# MP_MB_2014-12-17_B.net
KiCad netlist of a schematic drawn in Altium Designer
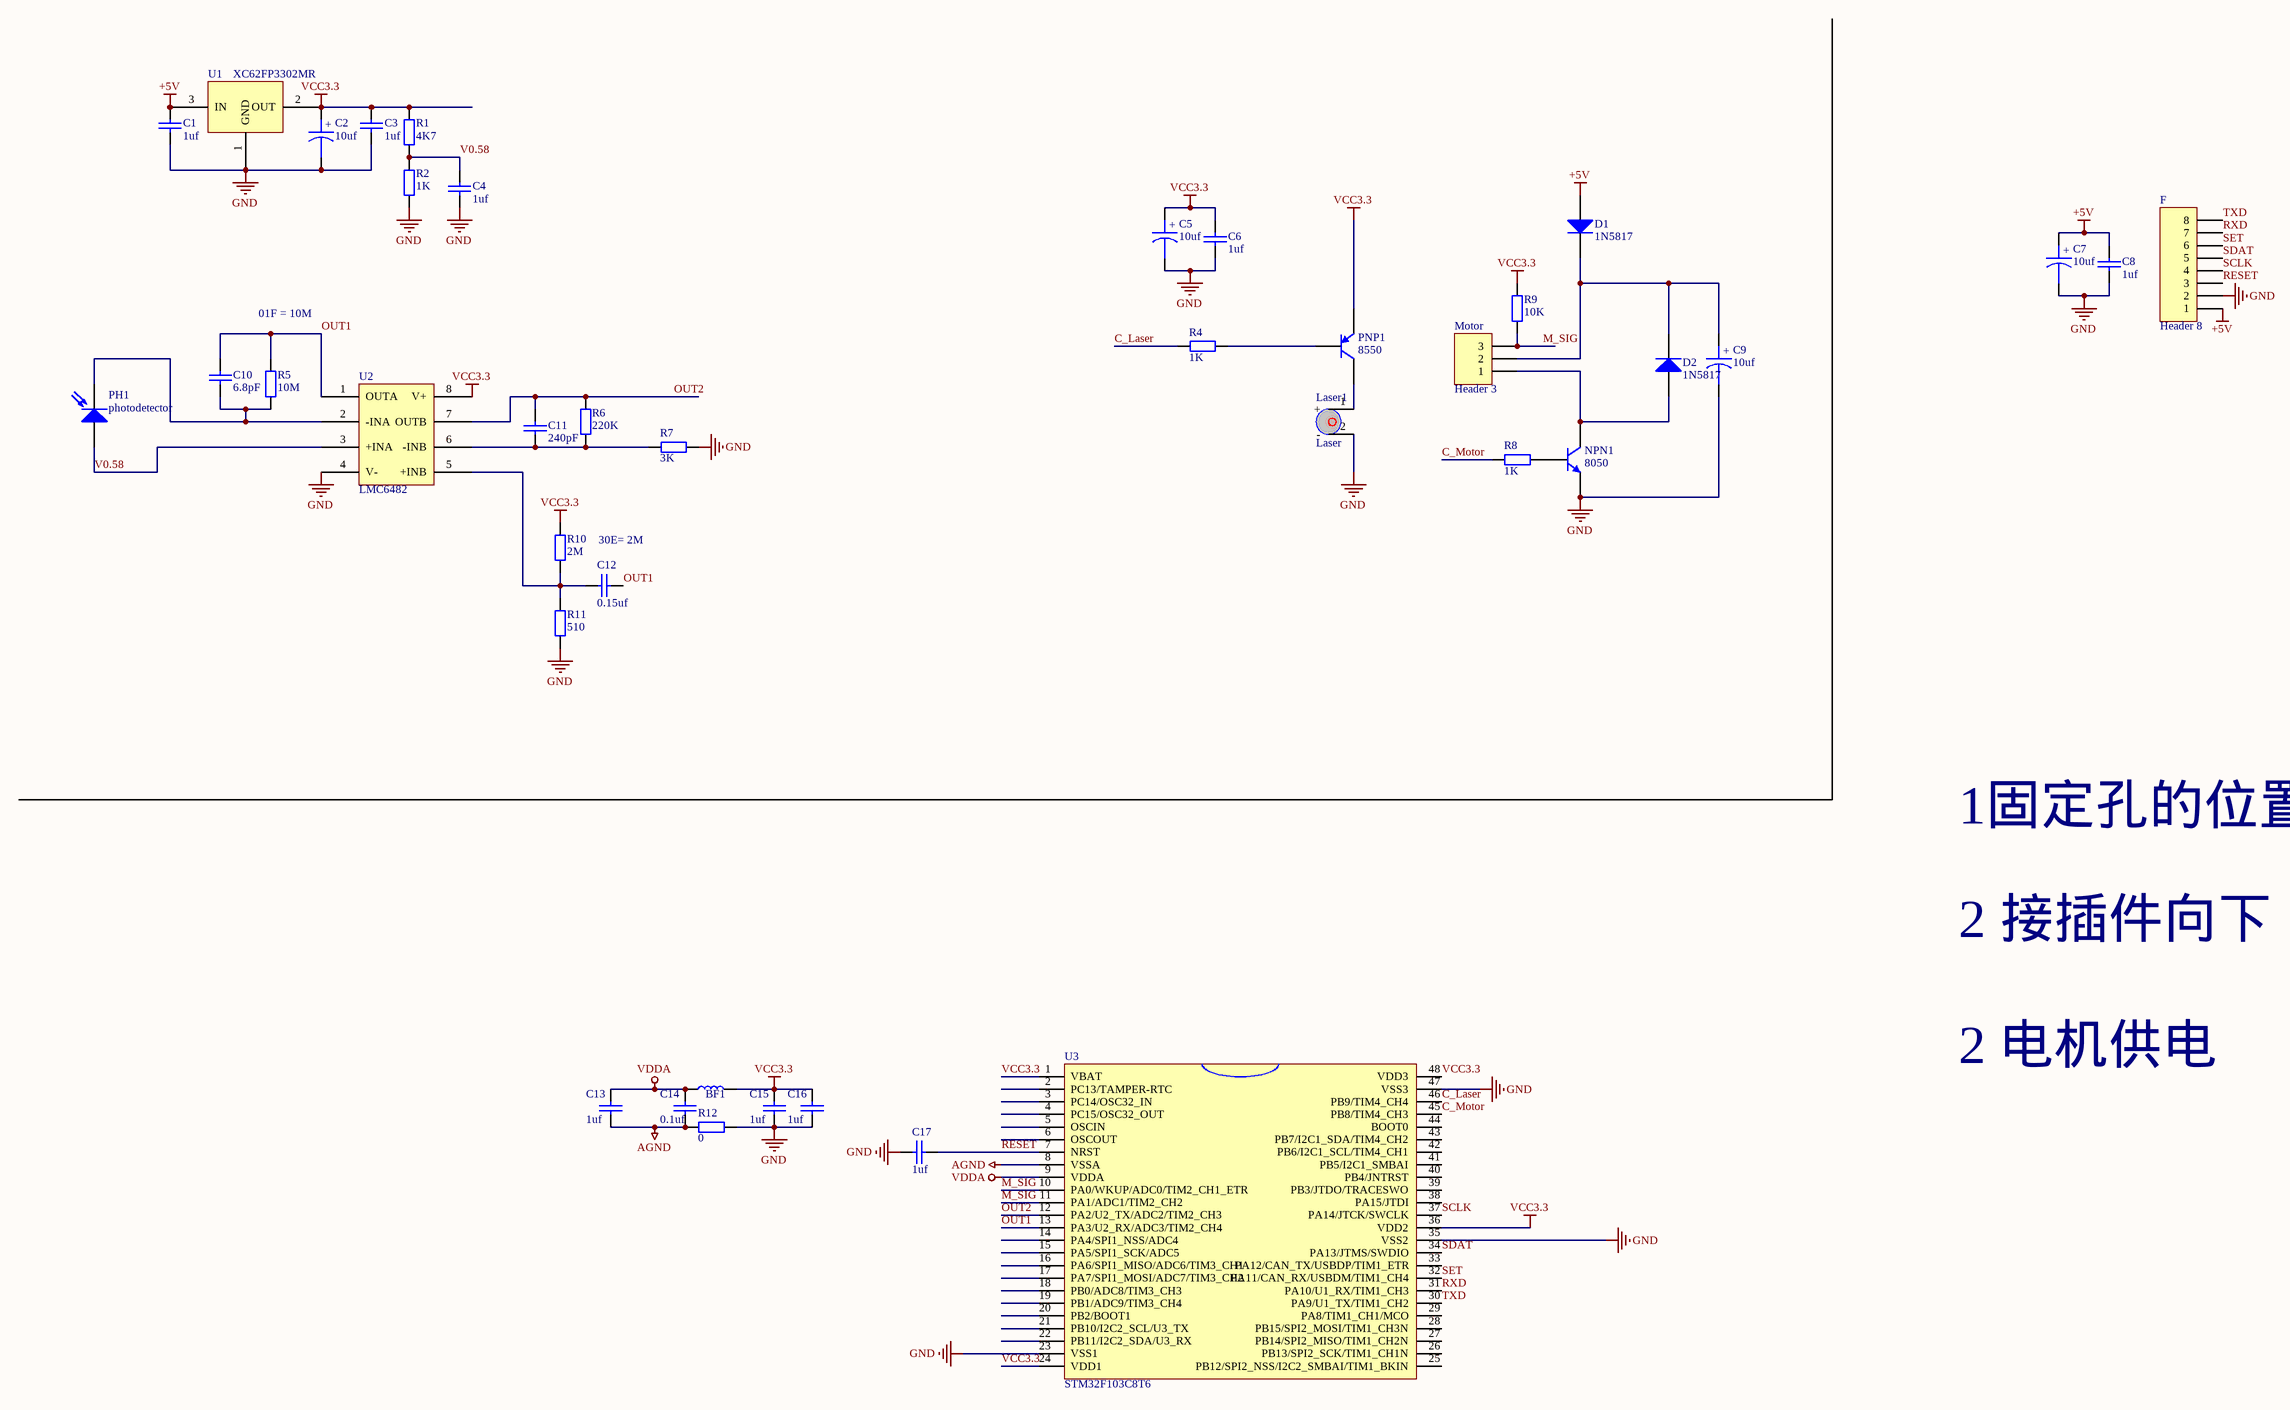
[diagram p0: MP_MB_2014-12-17_B.SchDoc]

(export (version "E")
  (design (tool "Eeschema 10.0.6"))
  (components
    (comp (ref "BF1")
      (value "BF")
      (footprint "R0603")
      (description "磁珠")
      (libsource (lib "SkyWorks") (part "BF"))
    )
    (comp (ref "C1") (value "1uf") (footprint "C0603") (libsource (lib "BHKSPRE") (part "C")))
    (comp (ref "C2") (value "10uf") (footprint "PolarC1206") (libsource (lib "BHKSPRE") (part "PolarCap")))
    (comp (ref "C3") (value "1uf") (footprint "C0603") (libsource (lib "BHKSPRE") (part "C")))
    (comp (ref "C4") (value "1uf") (footprint "C0603") (libsource (lib "BHKSPRE") (part "C")))
    (comp (ref "C5") (value "10uf") (footprint "PolarC1206") (libsource (lib "BHKSPRE") (part "PolarCap")))
    (comp (ref "C6") (value "1uf") (footprint "C0603") (libsource (lib "BHKSPRE") (part "C")))
    (comp (ref "C7") (value "10uf") (footprint "PolarC1206") (libsource (lib "BHKSPRE") (part "PolarCap")))
    (comp (ref "C8") (value "1uf") (footprint "C0603") (libsource (lib "BHKSPRE") (part "C")))
    (comp (ref "C9") (value "10uf") (footprint "PolarC1206") (libsource (lib "BHKSPRE") (part "PolarCap")))
    (comp (ref "C10") (value "6.8pF") (footprint "C0603") (libsource (lib "BHKSPRE") (part "C")))
    (comp (ref "C11") (value "240pF") (footprint "C0603") (libsource (lib "BHKSPRE") (part "C")))
    (comp (ref "C12") (value "0.15uf") (footprint "C0603") (libsource (lib "BHKSPRE") (part "C")))
    (comp (ref "C13") (value "1uf") (footprint "C0603") (libsource (lib "BHKSPRE") (part "C")))
    (comp (ref "C14") (value "0.1uf") (footprint "C0603") (libsource (lib "BHKSPRE") (part "C")))
    (comp (ref "C15") (value "1uf") (footprint "C0603") (libsource (lib "BHKSPRE") (part "C")))
    (comp (ref "C16") (value "1uf") (footprint "C0603") (libsource (lib "BHKSPRE") (part "C")))
    (comp (ref "C17") (value "1uf") (footprint "C0603") (libsource (lib "BHKSPRE") (part "C")))
    (comp (ref "D1") (value "1N5817") (footprint "Diode1206") (libsource (lib "BHKSPRE") (part "Diode")))
    (comp (ref "D2") (value "1N5817") (footprint "Diode1206") (libsource (lib "BHKSPRE") (part "Diode")))
    (comp (ref "F")
      (value "Header 8")
      (footprint "S-SIN-8")
      (description "Header, 8-Pin")
      (fields (field (name "PUBLISHER") "Altium Limited"))
      (libsource (lib "Miscellaneous Connectors") (part "Header 8"))
    )
    (comp (ref "Laser1") (value "Laser") (footprint "Laser") (libsource (lib "BHKSPRE") (part "Laser")))
    (comp (ref "Motor")
      (value "Header 3")
      (footprint "SIP3-1mm")
      (description "Header, 3-Pin")
      (fields (field (name "PUBLISHER") "Altium Limited"))
      (libsource (lib "Miscellaneous Connectors") (part "Header 3"))
    )
    (comp (ref "NPN1") (value "8050") (footprint "SOT23-3") (libsource (lib "BHKSPRE") (part "NPN")))
    (comp (ref "PH1") (value "photodetector") (footprint "BPW34") (libsource (lib "Sensor") (part "PH")))
    (comp (ref "PNP1") (value "8550") (footprint "SOT23-3") (libsource (lib "BHKSPRE") (part "PNP")))
    (comp (ref "R1") (value "4K7") (footprint "R0603") (libsource (lib "BHKSPRE") (part "R")))
    (comp (ref "R2") (value "1K") (footprint "R0603") (libsource (lib "BHKSPRE") (part "R")))
    (comp (ref "R4") (value "1K") (footprint "R0603") (libsource (lib "BHKSPRE") (part "R")))
    (comp (ref "R5") (value "10M") (footprint "R0603") (libsource (lib "BHKSPRE") (part "R")))
    (comp (ref "R6") (value "220K") (footprint "R0603") (libsource (lib "BHKSPRE") (part "R")))
    (comp (ref "R7") (value "3K") (footprint "R0603") (libsource (lib "BHKSPRE") (part "R")))
    (comp (ref "R8") (value "1K") (footprint "R0603") (libsource (lib "BHKSPRE") (part "R")))
    (comp (ref "R9") (value "10K") (footprint "R0603") (libsource (lib "BHKSPRE") (part "R")))
    (comp (ref "R10") (value "2M") (footprint "R0603") (libsource (lib "BHKSPRE") (part "R")))
    (comp (ref "R11") (value "510") (footprint "R0603") (libsource (lib "BHKSPRE") (part "R")))
    (comp (ref "R12") (value "0") (footprint "R0603") (libsource (lib "BHKSPRE") (part "R")))
    (comp (ref "U1")
      (value "XC62FP3302MR")
      (footprint "SOT23-3")
      (libsource (lib "SkyWorks") (part "XC62FP3302MR"))
    )
    (comp (ref "U2") (value "LMC6482") (footprint "SOP-8") (libsource (lib "VOC") (part "AD8629")))
    (comp (ref "U3")
      (value "STM32F103C8T6")
      (footprint "QFP-48")
      (libsource (lib "SkyWorks") (part "STM32F103C8T6"))
    )
  )
  (nets
    (net (code "1") (name "+5V") (class "Default")
      (node (ref "C1") (pin "1") (pinfunction "1_1") (pintype "passive"))
      (node (ref "C7") (pin "A") (pinfunction "A_A") (pintype "passive"))
      (node (ref "C8") (pin "1") (pinfunction "1_1") (pintype "passive"))
      (node (ref "D1") (pin "A") (pinfunction "A_A") (pintype "passive"))
      (node (ref "F") (pin "1") (pinfunction "1_1") (pintype "passive"))
      (node (ref "U1") (pin "3") (pinfunction "IN_3") (pintype "passive"))
    )
    (net (code "2") (name "/C_Laser") (class "Default")
      (node (ref "R4") (pin "2") (pinfunction "2_2") (pintype "passive"))
      (node (ref "U3") (pin "46") (pinfunction "PB9/TIM4_CH4_46") (pintype "passive"))
    )
    (net (code "3") (name "/C_Motor") (class "Default")
      (node (ref "R8") (pin "2") (pinfunction "2_2") (pintype "passive"))
      (node (ref "U3") (pin "45") (pinfunction "PB8/TIM4_CH3_45") (pintype "passive"))
    )
    (net (code "4") (name "/M_SIG") (class "Default")
      (node (ref "Motor") (pin "3") (pinfunction "3_3") (pintype "passive"))
      (node (ref "R9") (pin "1") (pinfunction "1_1") (pintype "passive"))
      (node (ref "U3") (pin "10") (pinfunction "PA0/WKUP/ADC0/TIM2_CH1_ETR_10") (pintype "passive"))
      (node (ref "U3") (pin "11") (pinfunction "PA1/ADC1/TIM2_CH2_11") (pintype "passive"))
    )
    (net (code "5") (name "/OUT1") (class "Default")
      (node (ref "C10") (pin "1") (pinfunction "1_1") (pintype "passive"))
      (node (ref "C12") (pin "2") (pinfunction "2_2") (pintype "passive"))
      (node (ref "R5") (pin "2") (pinfunction "2_2") (pintype "passive"))
      (node (ref "U2") (pin "1") (pinfunction "OUTA_1") (pintype "passive"))
      (node (ref "U3") (pin "13") (pinfunction "PA3/U2_RX/ADC3/TIM2_CH4_13") (pintype "passive"))
    )
    (net (code "6") (name "/OUT2") (class "Default")
      (node (ref "C11") (pin "1") (pinfunction "1_1") (pintype "passive"))
      (node (ref "R6") (pin "2") (pinfunction "2_2") (pintype "passive"))
      (node (ref "U2") (pin "7") (pinfunction "OUTB_7") (pintype "passive"))
      (node (ref "U3") (pin "12") (pinfunction "PA2/U2_TX/ADC2/TIM2_CH3_12") (pintype "passive"))
    )
    (net (code "7") (name "/RESET") (class "Default")
      (node (ref "C17") (pin "1") (pinfunction "1_1") (pintype "passive"))
      (node (ref "F") (pin "3") (pinfunction "3_3") (pintype "passive"))
      (node (ref "U3") (pin "7") (pinfunction "NRST_7") (pintype "passive"))
    )
    (net (code "8") (name "/RXD") (class "Default")
      (node (ref "F") (pin "7") (pinfunction "7_7") (pintype "passive"))
      (node (ref "U3") (pin "31") (pinfunction "PA10/U1_RX/TIM1_CH3_31") (pintype "passive"))
    )
    (net (code "9") (name "/SCLK") (class "Default")
      (node (ref "F") (pin "4") (pinfunction "4_4") (pintype "passive"))
      (node (ref "U3") (pin "37") (pinfunction "PA14/JTCK/SWCLK_37") (pintype "passive"))
    )
    (net (code "10") (name "/SDAT") (class "Default")
      (node (ref "F") (pin "5") (pinfunction "5_5") (pintype "passive"))
      (node (ref "U3") (pin "34") (pinfunction "PA13/JTMS/SWDIO_34") (pintype "passive"))
    )
    (net (code "11") (name "/SET") (class "Default")
      (node (ref "F") (pin "6") (pinfunction "6_6") (pintype "passive"))
      (node (ref "U3") (pin "32") (pinfunction "PA11/CAN_RX/USBDM/TIM1_CH4_32") (pintype "passive"))
    )
    (net (code "12") (name "/TXD") (class "Default")
      (node (ref "F") (pin "8") (pinfunction "8_8") (pintype "passive"))
      (node (ref "U3") (pin "30") (pinfunction "PA9/U1_TX/TIM1_CH2_30") (pintype "passive"))
    )
    (net (code "13") (name "/V0.58") (class "Default")
      (node (ref "C4") (pin "1") (pinfunction "1_1") (pintype "passive"))
      (node (ref "PH1") (pin "A") (pinfunction "A_A") (pintype "passive"))
      (node (ref "R1") (pin "1") (pinfunction "1_1") (pintype "passive"))
      (node (ref "R2") (pin "2") (pinfunction "2_2") (pintype "passive"))
      (node (ref "U2") (pin "3") (pinfunction "+INA_3") (pintype "passive"))
    )
    (net (code "14") (name "AGND") (class "Default")
      (node (ref "C13") (pin "1") (pinfunction "1_1") (pintype "passive"))
      (node (ref "C14") (pin "1") (pinfunction "1_1") (pintype "passive"))
      (node (ref "R12") (pin "2") (pinfunction "2_2") (pintype "passive"))
      (node (ref "U3") (pin "8") (pinfunction "VSSA_8") (pintype "passive"))
    )
    (net (code "15") (name "GND") (class "Default")
      (node (ref "C1") (pin "2") (pinfunction "2_2") (pintype "passive"))
      (node (ref "C15") (pin "1") (pinfunction "1_1") (pintype "passive"))
      (node (ref "C16") (pin "1") (pinfunction "1_1") (pintype "passive"))
      (node (ref "C17") (pin "2") (pinfunction "2_2") (pintype "passive"))
      (node (ref "C2") (pin "C") (pinfunction "C_C") (pintype "passive"))
      (node (ref "C3") (pin "2") (pinfunction "2_2") (pintype "passive"))
      (node (ref "C4") (pin "2") (pinfunction "2_2") (pintype "passive"))
      (node (ref "C5") (pin "C") (pinfunction "C_C") (pintype "passive"))
      (node (ref "C6") (pin "2") (pinfunction "2_2") (pintype "passive"))
      (node (ref "C7") (pin "C") (pinfunction "C_C") (pintype "passive"))
      (node (ref "C8") (pin "2") (pinfunction "2_2") (pintype "passive"))
      (node (ref "C9") (pin "C") (pinfunction "C_C") (pintype "passive"))
      (node (ref "F") (pin "2") (pinfunction "2_2") (pintype "passive"))
      (node (ref "Laser1") (pin "2") (pinfunction "-_2") (pintype "passive"))
      (node (ref "NPN1") (pin "2") (pinfunction "E_2") (pintype "passive"))
      (node (ref "R11") (pin "1") (pinfunction "1_1") (pintype "passive"))
      (node (ref "R12") (pin "1") (pinfunction "1_1") (pintype "passive"))
      (node (ref "R2") (pin "1") (pinfunction "1_1") (pintype "passive"))
      (node (ref "R7") (pin "1") (pinfunction "1_1") (pintype "passive"))
      (node (ref "U1") (pin "1") (pinfunction "GND_1") (pintype "passive"))
      (node (ref "U2") (pin "4") (pinfunction "V-_4") (pintype "passive"))
      (node (ref "U3") (pin "23") (pinfunction "VSS1_23") (pintype "passive"))
      (node (ref "U3") (pin "35") (pinfunction "VSS2_35") (pintype "passive"))
      (node (ref "U3") (pin "47") (pinfunction "VSS3_47") (pintype "passive"))
    )
    (net (code "16") (name "Net-(D1-K)") (class "Default")
      (node (ref "C9") (pin "A") (pinfunction "A_A") (pintype "passive"))
      (node (ref "D1") (pin "C") (pinfunction "K_C") (pintype "passive"))
      (node (ref "D2") (pin "C") (pinfunction "K_C") (pintype "passive"))
      (node (ref "Motor") (pin "2") (pinfunction "2_2") (pintype "passive"))
    )
    (net (code "17") (name "Net-(Laser1-+)") (class "Default")
      (node (ref "Laser1") (pin "1") (pinfunction "+_1") (pintype "passive"))
      (node (ref "PNP1") (pin "3") (pinfunction "C_3") (pintype "passive"))
    )
    (net (code "18") (name "Net-(NPN1-B)") (class "Default")
      (node (ref "NPN1") (pin "1") (pinfunction "B_1") (pintype "passive"))
      (node (ref "R8") (pin "1") (pinfunction "1_1") (pintype "passive"))
    )
    (net (code "19") (name "Net-(NPN1-C)") (class "Default")
      (node (ref "D2") (pin "A") (pinfunction "A_A") (pintype "passive"))
      (node (ref "Motor") (pin "1") (pinfunction "1_1") (pintype "passive"))
      (node (ref "NPN1") (pin "3") (pinfunction "C_3") (pintype "passive"))
    )
    (net (code "20") (name "Net-(PNP1-B)") (class "Default")
      (node (ref "PNP1") (pin "1") (pinfunction "B_1") (pintype "passive"))
      (node (ref "R4") (pin "1") (pinfunction "1_1") (pintype "passive"))
    )
    (net (code "21") (name "Net-(U2-+INB)") (class "Default")
      (node (ref "C12") (pin "1") (pinfunction "1_1") (pintype "passive"))
      (node (ref "R10") (pin "1") (pinfunction "1_1") (pintype "passive"))
      (node (ref "R11") (pin "2") (pinfunction "2_2") (pintype "passive"))
      (node (ref "U2") (pin "5") (pinfunction "+INB_5") (pintype "passive"))
    )
    (net (code "22") (name "Net-(U2--INA)") (class "Default")
      (node (ref "C10") (pin "2") (pinfunction "2_2") (pintype "passive"))
      (node (ref "PH1") (pin "C") (pinfunction "C_C") (pintype "passive"))
      (node (ref "R5") (pin "1") (pinfunction "1_1") (pintype "passive"))
      (node (ref "U2") (pin "2") (pinfunction "-INA_2") (pintype "passive"))
    )
    (net (code "23") (name "Net-(U2--INB)") (class "Default")
      (node (ref "C11") (pin "2") (pinfunction "2_2") (pintype "passive"))
      (node (ref "R6") (pin "1") (pinfunction "1_1") (pintype "passive"))
      (node (ref "R7") (pin "2") (pinfunction "2_2") (pintype "passive"))
      (node (ref "U2") (pin "6") (pinfunction "-INB_6") (pintype "passive"))
    )
    (net (code "24") (name "VCC3.3") (class "Default")
      (node (ref "BF1") (pin "2") (pinfunction "2_2") (pintype "passive"))
      (node (ref "C15") (pin "2") (pinfunction "2_2") (pintype "passive"))
      (node (ref "C16") (pin "2") (pinfunction "2_2") (pintype "passive"))
      (node (ref "C2") (pin "A") (pinfunction "A_A") (pintype "passive"))
      (node (ref "C3") (pin "1") (pinfunction "1_1") (pintype "passive"))
      (node (ref "C5") (pin "A") (pinfunction "A_A") (pintype "passive"))
      (node (ref "C6") (pin "1") (pinfunction "1_1") (pintype "passive"))
      (node (ref "PNP1") (pin "2") (pinfunction "E_2") (pintype "passive"))
      (node (ref "R1") (pin "2") (pinfunction "2_2") (pintype "passive"))
      (node (ref "R10") (pin "2") (pinfunction "2_2") (pintype "passive"))
      (node (ref "R9") (pin "2") (pinfunction "2_2") (pintype "passive"))
      (node (ref "U1") (pin "2") (pinfunction "OUT_2") (pintype "passive"))
      (node (ref "U2") (pin "8") (pinfunction "V+_8") (pintype "passive"))
      (node (ref "U3") (pin "1") (pinfunction "VBAT_1") (pintype "passive"))
      (node (ref "U3") (pin "24") (pinfunction "VDD1_24") (pintype "passive"))
      (node (ref "U3") (pin "36") (pinfunction "VDD2_36") (pintype "passive"))
      (node (ref "U3") (pin "48") (pinfunction "VDD3_48") (pintype "passive"))
    )
    (net (code "25") (name "VDDA") (class "Default")
      (node (ref "BF1") (pin "1") (pinfunction "1_1") (pintype "passive"))
      (node (ref "C13") (pin "2") (pinfunction "2_2") (pintype "passive"))
      (node (ref "C14") (pin "2") (pinfunction "2_2") (pintype "passive"))
      (node (ref "U3") (pin "9") (pinfunction "VDDA_9") (pintype "passive"))
    )
    (net (code "26") (name "unconnected-(U3-BOOT0-Pad44)") (class "Default")
      (node (ref "U3") (pin "44") (pinfunction "BOOT0_44") (pintype "passive"))
    )
    (net (code "27") (name "unconnected-(U3-OSCIN-Pad5)") (class "Default")
      (node (ref "U3") (pin "5") (pinfunction "OSCIN_5") (pintype "passive"))
    )
    (net (code "28") (name "unconnected-(U3-OSCOUT-Pad6)") (class "Default")
      (node (ref "U3") (pin "6") (pinfunction "OSCOUT_6") (pintype "passive"))
    )
    (net (code "29") (name "unconnected-(U3-PA4{slash}SPI1_NSS{slash}ADC4-Pad14)") (class "Default")
      (node (ref "U3") (pin "14") (pinfunction "PA4/SPI1_NSS/ADC4_14") (pintype "passive"))
    )
    (net (code "30") (name "unconnected-(U3-PA5{slash}SPI1_SCK{slash}ADC5-Pad15)") (class "Default")
      (node (ref "U3") (pin "15") (pinfunction "PA5/SPI1_SCK/ADC5_15") (pintype "passive"))
    )
    (net (code "31") (name "unconnected-(U3-PA6{slash}SPI1_MISO{slash}ADC6{slash}TIM3_CH1-Pad16)") (class "Default")
      (node (ref "U3") (pin "16") (pinfunction "PA6/SPI1_MISO/ADC6/TIM3_CH1_16") (pintype "passive"))
    )
    (net (code "32") (name "unconnected-(U3-PA7{slash}SPI1_MOSI{slash}ADC7{slash}TIM3_CH2-Pad17)") (class "Default")
      (node (ref "U3") (pin "17") (pinfunction "PA7/SPI1_MOSI/ADC7/TIM3_CH2_17") (pintype "passive"))
    )
    (net (code "33") (name "unconnected-(U3-PA8{slash}TIM1_CH1{slash}MCO-Pad29)") (class "Default")
      (node (ref "U3") (pin "29") (pinfunction "PA8/TIM1_CH1/MCO_29") (pintype "passive"))
    )
    (net (code "34") (name "unconnected-(U3-PA12{slash}CAN_TX{slash}USBDP{slash}TIM1_ETR-Pad33)") (class "Default")
      (node (ref "U3") (pin "33") (pinfunction "PA12/CAN_TX/USBDP/TIM1_ETR_33") (pintype "passive"))
    )
    (net (code "35") (name "unconnected-(U3-PA15{slash}JTDI-Pad38)") (class "Default")
      (node (ref "U3") (pin "38") (pinfunction "PA15/JTDI_38") (pintype "passive"))
    )
    (net (code "36") (name "unconnected-(U3-PB0{slash}ADC8{slash}TIM3_CH3-Pad18)") (class "Default")
      (node (ref "U3") (pin "18") (pinfunction "PB0/ADC8/TIM3_CH3_18") (pintype "passive"))
    )
    (net (code "37") (name "unconnected-(U3-PB1{slash}ADC9{slash}TIM3_CH4-Pad19)") (class "Default")
      (node (ref "U3") (pin "19") (pinfunction "PB1/ADC9/TIM3_CH4_19") (pintype "passive"))
    )
    (net (code "38") (name "unconnected-(U3-PB2{slash}BOOT1-Pad20)") (class "Default")
      (node (ref "U3") (pin "20") (pinfunction "PB2/BOOT1_20") (pintype "passive"))
    )
    (net (code "39") (name "unconnected-(U3-PB3{slash}JTDO{slash}TRACESWO-Pad39)") (class "Default")
      (node (ref "U3") (pin "39") (pinfunction "PB3/JTDO/TRACESWO_39") (pintype "passive"))
    )
    (net (code "40") (name "unconnected-(U3-PB4{slash}JNTRST-Pad40)") (class "Default")
      (node (ref "U3") (pin "40") (pinfunction "PB4/JNTRST_40") (pintype "passive"))
    )
    (net (code "41") (name "unconnected-(U3-PB5{slash}I2C1_SMBAI-Pad41)") (class "Default")
      (node (ref "U3") (pin "41") (pinfunction "PB5/I2C1_SMBAI_41") (pintype "passive"))
    )
    (net (code "42") (name "unconnected-(U3-PB6{slash}I2C1_SCL{slash}TIM4_CH1-Pad42)") (class "Default")
      (node (ref "U3") (pin "42") (pinfunction "PB6/I2C1_SCL/TIM4_CH1_42") (pintype "passive"))
    )
    (net (code "43") (name "unconnected-(U3-PB7{slash}I2C1_SDA{slash}TIM4_CH2-Pad43)") (class "Default")
      (node (ref "U3") (pin "43") (pinfunction "PB7/I2C1_SDA/TIM4_CH2_43") (pintype "passive"))
    )
    (net (code "44") (name "unconnected-(U3-PB10{slash}I2C2_SCL{slash}U3_TX-Pad21)") (class "Default")
      (node (ref "U3") (pin "21") (pinfunction "PB10/I2C2_SCL/U3_TX_21") (pintype "passive"))
    )
    (net (code "45") (name "unconnected-(U3-PB11{slash}I2C2_SDA{slash}U3_RX-Pad22)") (class "Default")
      (node (ref "U3") (pin "22") (pinfunction "PB11/I2C2_SDA/U3_RX_22") (pintype "passive"))
    )
    (net (code "46") (name "unconnected-(U3-PB12{slash}SPI2_NSS{slash}I2C2_SMBAI{slash}TIM1_BKIN-Pad25)") (class "Default")
      (node (ref "U3") (pin "25") (pinfunction "PB12/SPI2_NSS/I2C2_SMBAI/TIM1_BKIN_25") (pintype "passive"))
    )
    (net (code "47") (name "unconnected-(U3-PB13{slash}SPI2_SCK{slash}TIM1_CH1N-Pad26)") (class "Default")
      (node (ref "U3") (pin "26") (pinfunction "PB13/SPI2_SCK/TIM1_CH1N_26") (pintype "passive"))
    )
    (net (code "48") (name "unconnected-(U3-PB14{slash}SPI2_MISO{slash}TIM1_CH2N-Pad27)") (class "Default")
      (node (ref "U3") (pin "27") (pinfunction "PB14/SPI2_MISO/TIM1_CH2N_27") (pintype "passive"))
    )
    (net (code "49") (name "unconnected-(U3-PB15{slash}SPI2_MOSI{slash}TIM1_CH3N-Pad28)") (class "Default")
      (node (ref "U3") (pin "28") (pinfunction "PB15/SPI2_MOSI/TIM1_CH3N_28") (pintype "passive"))
    )
    (net (code "50") (name "unconnected-(U3-PC13{slash}TAMPER-RTC-Pad2)") (class "Default")
      (node (ref "U3") (pin "2") (pinfunction "PC13/TAMPER-RTC_2") (pintype "passive"))
    )
    (net (code "51") (name "unconnected-(U3-PC14{slash}OSC32_IN-Pad3)") (class "Default")
      (node (ref "U3") (pin "3") (pinfunction "PC14/OSC32_IN_3") (pintype "passive"))
    )
    (net (code "52") (name "unconnected-(U3-PC15{slash}OSC32_OUT-Pad4)") (class "Default")
      (node (ref "U3") (pin "4") (pinfunction "PC15/OSC32_OUT_4") (pintype "passive"))
    )
  )
)
